# Perifericos.net
KiCad netlist of a schematic drawn in Altium Designer
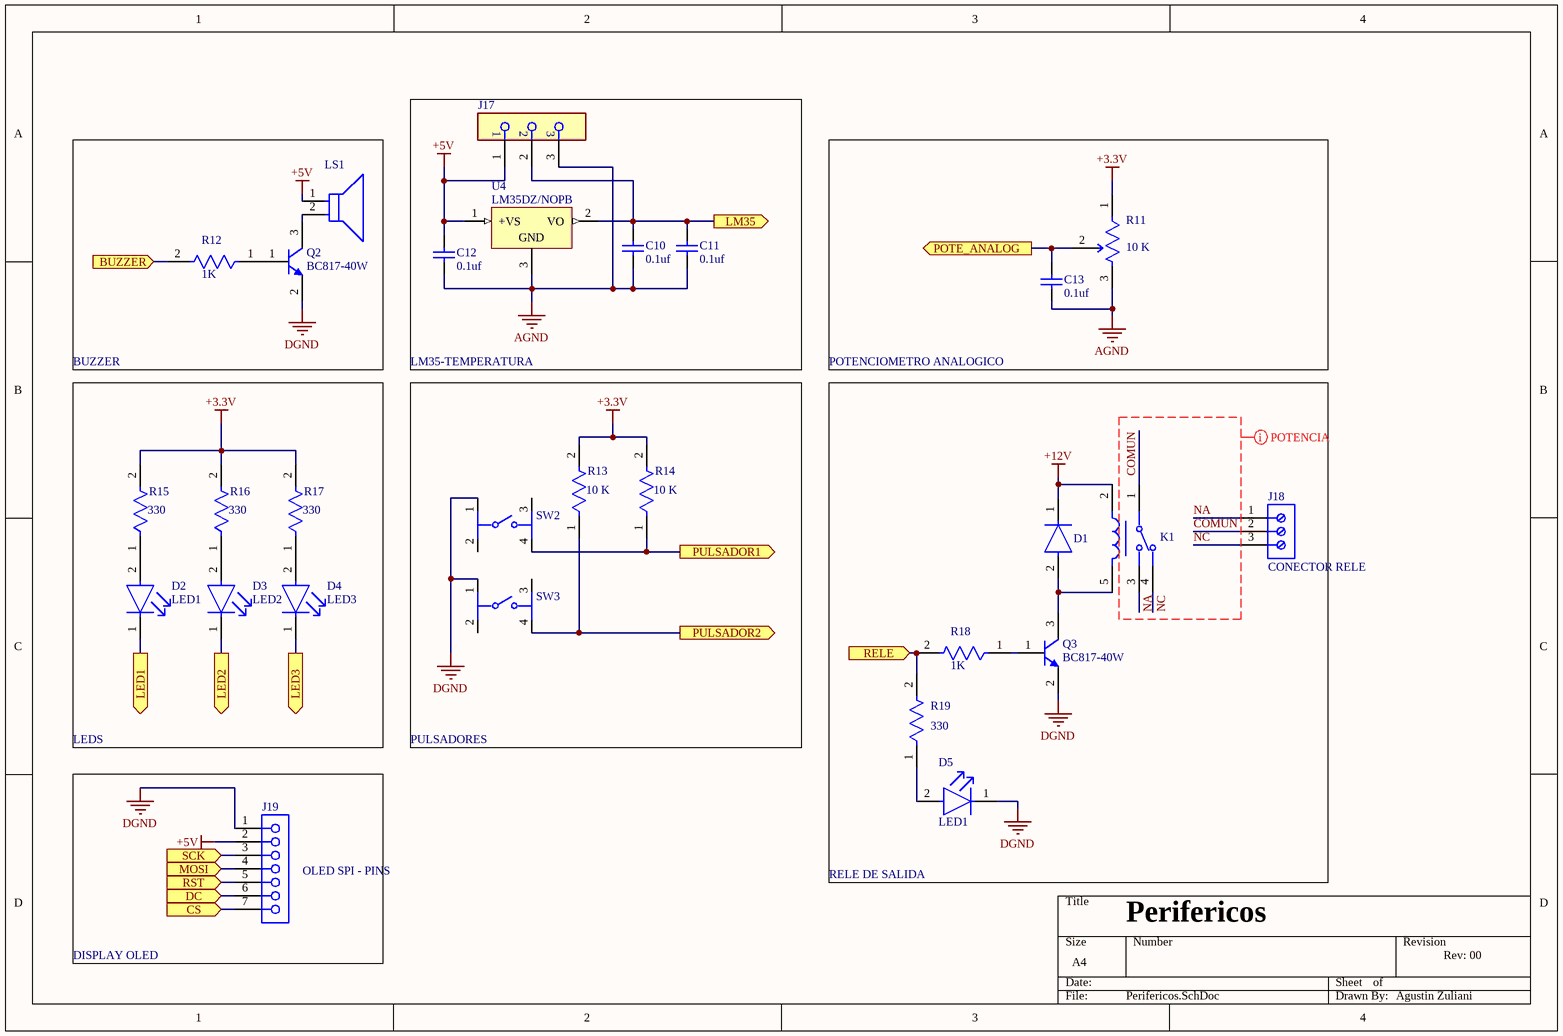
[diagram p0: Perifericos.SchDoc]

(export (version "E")
  (design (tool "Eeschema 10.0.6"))
  (components
    (comp (ref "C10")
      (value "0.1uf")
      (footprint "CAPC2013X145X50NL20T25")
      (description "CAP 100nf 20% 0805")
      (fields (field (name "MANUFACTURER") "Kemet") (field (name "PART NUMBER") "C0805S104K5RACTU"))
      (libsource (lib "Altium Content Vault") (part "CAP"))
    )
    (comp (ref "C11")
      (value "0.1uf")
      (footprint "CAPC2013X145X50NL20T25")
      (description "CAP 100nf 20% 0805")
      (fields (field (name "MANUFACTURER") "Kemet") (field (name "PART NUMBER") "C0805S104K5RACTU"))
      (libsource (lib "Altium Content Vault") (part "CAP"))
    )
    (comp (ref "C12")
      (value "0.1uf")
      (footprint "CAPC2013X145X50NL20T25")
      (description "CAP 100nf 20% 0805")
      (fields (field (name "MANUFACTURER") "Kemet") (field (name "PART NUMBER") "C0805S104K5RACTU"))
      (libsource (lib "Altium Content Vault") (part "CAP"))
    )
    (comp (ref "C13")
      (value "0.1uf")
      (footprint "CAPC2013X145X50NL20T25")
      (description "CAP 100nf 20% 0805")
      (fields (field (name "MANUFACTURER") "Kemet") (field (name "PART NUMBER") "C0805S104K5RACTU"))
      (libsource (lib "Altium Content Vault") (part "CAP"))
    )
    (comp (ref "D1")
      (value "1N4007 SMD")
      (footprint "FP-1N4007_SMD-IPC_C")
      (description "DIODE 1N4148 RELE PROTECTION")
      (libsource (lib "Altium Content Vault") (part "d7152d700b627762746794eb795d46e"))
    )
    (comp (ref "D2")
      (value "LED1")
      (footprint "FP-SML-LX0805UWC-TR-MFG")
      (description "LED SMD 0805")
      (libsource (lib "Altium Content Vault") (part "8706943c75ba83719d021d2fdc84c58"))
    )
    (comp (ref "D3")
      (value "LED2")
      (footprint "FP-SML-LX0805UWC-TR-MFG")
      (description "LED SMD 0805")
      (libsource (lib "Altium Content Vault") (part "8706943c75ba83719d021d2fdc84c58"))
    )
    (comp (ref "D4")
      (value "LED3")
      (footprint "FP-SML-LX0805UWC-TR-MFG")
      (description "LED SMD 0805")
      (libsource (lib "Altium Content Vault") (part "8706943c75ba83719d021d2fdc84c58"))
    )
    (comp (ref "D5")
      (value "LED1")
      (footprint "FP-SML-LX0805UWC-TR-MFG")
      (description "LED SMD 0805 / Rele status")
      (libsource (lib "Altium Content Vault") (part "8706943c75ba83719d021d2fdc84c58"))
    )
    (comp (ref "J17")
      (value "SSQ-103-01-T-S")
      (footprint "FP-SSQ-103-01-T-S-MFG")
      (description "HEADER PINS 3 POS / LM35 Pins")
      (libsource (lib "Altium Content Vault") (part "9e3c5d0b45d2cf0495be8a0529c1856"))
    )
    (comp (ref "J18")
      (value "CONECTOR RELE")
      (footprint "691216710003")
      (description "TERMINAL BLOCK 3 POS / Salida Rele")
      (libsource (lib "Altium Content Vault") (part "TBL - 1R - 03P - Screw"))
    )
    (comp (ref "J19")
      (value "OLED SPI - PINS")
      (footprint "61300711821")
      (description "HEADER PINS 7 POS / Pins Display OLED")
      (libsource (lib "Altium Content Vault") (part "Header_Female_1R_07P"))
    )
    (comp (ref "K1")
      (value "G5LE-1-E DC5")
      (footprint "FP-G5LE-1-E_DC5-MFG")
      (description "RELAY")
      (libsource (lib "Altium Content Vault") (part "c03b8d08e5d02e70a6880f365e34168"))
    )
    (comp (ref "LS1")
      (value "AT-1224-TWT-5V-2-R")
      (footprint "FP-AT-1224-TWT-5V-2-R-MFG")
      (description "BUZZER MAGNETIC 5V 12MM TH")
      (libsource (lib "Altium Content Vault") (part "1973c4b650225fd2ddacaff6b763965"))
    )
    (comp (ref "Q2")
      (value "BC817-40W")
      (footprint "DIOD-SOT323-3_V")
      (description "BJT NPN BC817 / Buzzer")
      (fields (field (name "MANUFACTURER") "DiodesIncorporated"))
      (libsource (lib "Altium Content Vault") (part "BJT-NPN-BEC-3"))
    )
    (comp (ref "Q3")
      (value "BC817-40W")
      (footprint "DIOD-SOT323-3_V")
      (description "BJT NPN BC817 SOT323 / Rele")
      (fields (field (name "MANUFACTURER") "DiodesIncorporated"))
      (libsource (lib "Altium Content Vault") (part "BJT-NPN-BEC-3"))
    )
    (comp (ref "R11")
      (value "10 K")
      (footprint "FP-COM-09806-MFG")
      (description "RES TRIMMER 10K 5% THT")
      (fields (field (name "TOLERANCE") "10%"))
      (libsource (lib "Altium Content Vault") (part "f4a88d01fac06fcc185e0159723c69e"))
    )
    (comp (ref "R12")
      (value "1K")
      (footprint "FP-RN73R2A-IPC_A")
      (description "RES 1K 5% 0805 / Buzzer")
      (libsource (lib "Altium Content Vault") (part "1029c3af85768c4190bb7ad29bc67b5"))
    )
    (comp (ref "R13")
      (value "10 K")
      (footprint "FP-RN73R2A-IPC_A")
      (description "RES 10K 5% 0805")
      (libsource (lib "Altium Content Vault") (part "1029c3af85768c4190bb7ad29bc67b5"))
    )
    (comp (ref "R14")
      (value "10 K")
      (footprint "FP-RN73R2A-IPC_A")
      (description "RES 10K 5% 0805")
      (libsource (lib "Altium Content Vault") (part "1029c3af85768c4190bb7ad29bc67b5"))
    )
    (comp (ref "R15")
      (value "330")
      (footprint "FP-RN73R2A-IPC_A")
      (description "RES 330R 5% 0805")
      (libsource (lib "Altium Content Vault") (part "1029c3af85768c4190bb7ad29bc67b5"))
    )
    (comp (ref "R16")
      (value "330")
      (footprint "FP-RN73R2A-IPC_A")
      (description "RES 330R 5% 0805")
      (libsource (lib "Altium Content Vault") (part "1029c3af85768c4190bb7ad29bc67b5"))
    )
    (comp (ref "R17")
      (value "330")
      (footprint "FP-RN73R2A-IPC_A")
      (description "RES 330R 5% 0805")
      (libsource (lib "Altium Content Vault") (part "1029c3af85768c4190bb7ad29bc67b5"))
    )
    (comp (ref "R18")
      (value "1K")
      (footprint "FP-RN73R2A-IPC_A")
      (description "RES 1K 5% 0805 / Rele")
      (libsource (lib "Altium Content Vault") (part "1029c3af85768c4190bb7ad29bc67b5"))
    )
    (comp (ref "R19")
      (value "330")
      (footprint "FP-RN73R2A-IPC_A")
      (description "RES 330R 5% 0805 / Rele")
      (libsource (lib "Altium Content Vault") (part "1029c3af85768c4190bb7ad29bc67b5"))
    )
    (comp (ref "SW2")
      (value "1-1825910-4")
      (footprint "FP-1-1825910-4-MFG")
      (description "SWITCH TACTILE 6mm / Pulsador 1")
      (fields
        (field (name "OCTOPART") "https://octopart.com/1-1825910-4-te+connectivity-42270468")
        (field (name "MANUFACTURER") "TE Connectivity")
      )
      (libsource (lib "Altium Content Vault") (part "b8895f3f4cefb76e1819d2863dba89b"))
    )
    (comp (ref "SW3")
      (value "1-1825910-4")
      (footprint "FP-1-1825910-4-MFG")
      (description "SWITCH TACTILE 6mm / Pulsador 2")
      (fields
        (field (name "OCTOPART") "https://octopart.com/1-1825910-4-te+connectivity-42270468")
        (field (name "MANUFACTURER") "TE Connectivity")
      )
      (libsource (lib "Altium Content Vault") (part "b8895f3f4cefb76e1819d2863dba89b"))
    )
    (comp (ref "U4")
      (value "LM35DZ/NOPB")
      (footprint "LP0003A")
      (description "CI LM35 TO92")
      (fields (field (name "MANUFACTURER") "Texas Instruments"))
      (libsource (lib "Altium Content Vault") (part "SEN-TEMP-LM34AH-3"))
    )
  )
  (nets
    (net (code "1") (name "+3.3V") (class "Default")
      (node (ref "R11") (pin "1") (pinfunction "CW_1") (pintype "passive"))
      (node (ref "R13") (pin "2") (pinfunction "2_2") (pintype "passive"))
      (node (ref "R14") (pin "2") (pinfunction "2_2") (pintype "passive"))
      (node (ref "R15") (pin "2") (pinfunction "2_2") (pintype "passive"))
      (node (ref "R16") (pin "2") (pinfunction "2_2") (pintype "passive"))
      (node (ref "R17") (pin "2") (pinfunction "2_2") (pintype "passive"))
    )
    (net (code "2") (name "+5V") (class "Default")
      (node (ref "C12") (pin "2") (pinfunction "2_2") (pintype "passive"))
      (node (ref "J17") (pin "1") (pinfunction "1_1") (pintype "passive"))
      (node (ref "J19") (pin "2") (pinfunction "2_2") (pintype "passive"))
      (node (ref "LS1") (pin "1") (pinfunction "C_1") (pintype "passive"))
      (node (ref "U4") (pin "1") (pinfunction "+VS_1") (pintype "input"))
    )
    (net (code "3") (name "+12V") (class "Default")
      (node (ref "D1") (pin "1") (pinfunction "C_1") (pintype "passive"))
      (node (ref "K1") (pin "2") (pinfunction "2_2") (pintype "passive"))
    )
    (net (code "4") (name "/BUZZER") (class "Default")
      (node (ref "R12") (pin "2") (pinfunction "2_2") (pintype "passive"))
    )
    (net (code "5") (name "/COMUN") (class "Default")
      (node (ref "J18") (pin "2") (pinfunction "2_2") (pintype "passive"))
      (node (ref "K1") (pin "1") (pinfunction "1_1") (pintype "passive"))
    )
    (net (code "6") (name "/CS") (class "Default")
      (node (ref "J19") (pin "7") (pinfunction "7_7") (pintype "passive"))
    )
    (net (code "7") (name "/DC") (class "Default")
      (node (ref "J19") (pin "6") (pinfunction "6_6") (pintype "passive"))
    )
    (net (code "8") (name "/LED1") (class "Default")
      (node (ref "D2") (pin "1") (pinfunction "C_1") (pintype "passive"))
    )
    (net (code "9") (name "/LED2") (class "Default")
      (node (ref "D3") (pin "1") (pinfunction "C_1") (pintype "passive"))
    )
    (net (code "10") (name "/LED3") (class "Default")
      (node (ref "D4") (pin "1") (pinfunction "C_1") (pintype "passive"))
    )
    (net (code "11") (name "/LM35") (class "Default")
      (node (ref "C10") (pin "2") (pinfunction "2_2") (pintype "passive"))
      (node (ref "C11") (pin "2") (pinfunction "2_2") (pintype "passive"))
      (node (ref "J17") (pin "2") (pinfunction "2_2") (pintype "passive"))
      (node (ref "U4") (pin "2") (pinfunction "VO_2") (pintype "output"))
    )
    (net (code "12") (name "/MOSI") (class "Default")
      (node (ref "J19") (pin "4") (pinfunction "4_4") (pintype "passive"))
    )
    (net (code "13") (name "/NA") (class "Default")
      (node (ref "J18") (pin "1") (pinfunction "1_1") (pintype "passive"))
      (node (ref "K1") (pin "3") (pinfunction "3_3") (pintype "passive"))
    )
    (net (code "14") (name "/NC") (class "Default")
      (node (ref "J18") (pin "3") (pinfunction "3_3") (pintype "passive"))
      (node (ref "K1") (pin "4") (pinfunction "4_4") (pintype "passive"))
    )
    (net (code "15") (name "/POTE_ANALOG") (class "Default")
      (node (ref "C13") (pin "2") (pinfunction "2_2") (pintype "passive"))
      (node (ref "R11") (pin "2") (pinfunction "WIPER_2") (pintype "passive"))
    )
    (net (code "16") (name "/PULSADOR1") (class "Default")
      (node (ref "R14") (pin "1") (pinfunction "1_1") (pintype "passive"))
      (node (ref "SW2") (pin "4") (pinfunction "4_4") (pintype "passive"))
    )
    (net (code "17") (name "/PULSADOR2") (class "Default")
      (node (ref "R13") (pin "1") (pinfunction "1_1") (pintype "passive"))
      (node (ref "SW3") (pin "4") (pinfunction "4_4") (pintype "passive"))
    )
    (net (code "18") (name "/RELE") (class "Default")
      (node (ref "R18") (pin "2") (pinfunction "2_2") (pintype "passive"))
      (node (ref "R19") (pin "2") (pinfunction "2_2") (pintype "passive"))
    )
    (net (code "19") (name "/RST") (class "Default")
      (node (ref "J19") (pin "5") (pinfunction "5_5") (pintype "passive"))
    )
    (net (code "20") (name "/SCK") (class "Default")
      (node (ref "J19") (pin "3") (pinfunction "3_3") (pintype "passive"))
    )
    (net (code "21") (name "AGND") (class "Default")
      (node (ref "C10") (pin "1") (pinfunction "1_1") (pintype "passive"))
      (node (ref "C11") (pin "1") (pinfunction "1_1") (pintype "passive"))
      (node (ref "C12") (pin "1") (pinfunction "1_1") (pintype "passive"))
      (node (ref "C13") (pin "1") (pinfunction "1_1") (pintype "passive"))
      (node (ref "J17") (pin "3") (pinfunction "3_3") (pintype "passive"))
      (node (ref "R11") (pin "3") (pinfunction "CCW_3") (pintype "passive"))
      (node (ref "U4") (pin "3") (pinfunction "GND_3") (pintype "power_in"))
    )
    (net (code "22") (name "DGND") (class "Default")
      (node (ref "D5") (pin "1") (pinfunction "C_1") (pintype "passive"))
      (node (ref "J19") (pin "1") (pinfunction "1_1") (pintype "passive"))
      (node (ref "Q2") (pin "2") (pinfunction "E_2") (pintype "passive"))
      (node (ref "Q3") (pin "2") (pinfunction "E_2") (pintype "passive"))
      (node (ref "SW2") (pin "1") (pinfunction "1_1") (pintype "passive"))
      (node (ref "SW3") (pin "1") (pinfunction "1_1") (pintype "passive"))
    )
    (net (code "23") (name "Net-(D1-A)") (class "Default")
      (node (ref "D1") (pin "2") (pinfunction "A_2") (pintype "passive"))
      (node (ref "K1") (pin "5") (pinfunction "5_5") (pintype "passive"))
      (node (ref "Q3") (pin "3") (pinfunction "C_3") (pintype "passive"))
    )
    (net (code "24") (name "Net-(D2-A)") (class "Default")
      (node (ref "D2") (pin "2") (pinfunction "A_2") (pintype "passive"))
      (node (ref "R15") (pin "1") (pinfunction "1_1") (pintype "passive"))
    )
    (net (code "25") (name "Net-(D3-A)") (class "Default")
      (node (ref "D3") (pin "2") (pinfunction "A_2") (pintype "passive"))
      (node (ref "R16") (pin "1") (pinfunction "1_1") (pintype "passive"))
    )
    (net (code "26") (name "Net-(D4-A)") (class "Default")
      (node (ref "D4") (pin "2") (pinfunction "A_2") (pintype "passive"))
      (node (ref "R17") (pin "1") (pinfunction "1_1") (pintype "passive"))
    )
    (net (code "27") (name "Net-(D5-A)") (class "Default")
      (node (ref "D5") (pin "2") (pinfunction "A_2") (pintype "passive"))
      (node (ref "R19") (pin "1") (pinfunction "1_1") (pintype "passive"))
    )
    (net (code "28") (name "Net-(LS1-A)") (class "Default")
      (node (ref "LS1") (pin "2") (pinfunction "A_2") (pintype "passive"))
      (node (ref "Q2") (pin "3") (pinfunction "C_3") (pintype "passive"))
    )
    (net (code "29") (name "Net-(Q2-B)") (class "Default")
      (node (ref "Q2") (pin "1") (pinfunction "B_1") (pintype "passive"))
      (node (ref "R12") (pin "1") (pinfunction "1_1") (pintype "passive"))
    )
    (net (code "30") (name "Net-(Q3-B)") (class "Default")
      (node (ref "Q3") (pin "1") (pinfunction "B_1") (pintype "passive"))
      (node (ref "R18") (pin "1") (pinfunction "1_1") (pintype "passive"))
    )
    (net (code "31") (name "unconnected-(SW2-Pad2)") (class "Default")
      (node (ref "SW2") (pin "2") (pinfunction "2_2") (pintype "passive"))
    )
    (net (code "32") (name "unconnected-(SW2-Pad3)") (class "Default")
      (node (ref "SW2") (pin "3") (pinfunction "3_3") (pintype "passive"))
    )
    (net (code "33") (name "unconnected-(SW3-Pad2)") (class "Default")
      (node (ref "SW3") (pin "2") (pinfunction "2_2") (pintype "passive"))
    )
    (net (code "34") (name "unconnected-(SW3-Pad3)") (class "Default")
      (node (ref "SW3") (pin "3") (pinfunction "3_3") (pintype "passive"))
    )
  )
)
